# Monitor3.net
KiCad netlist of a schematic drawn in EAGLE
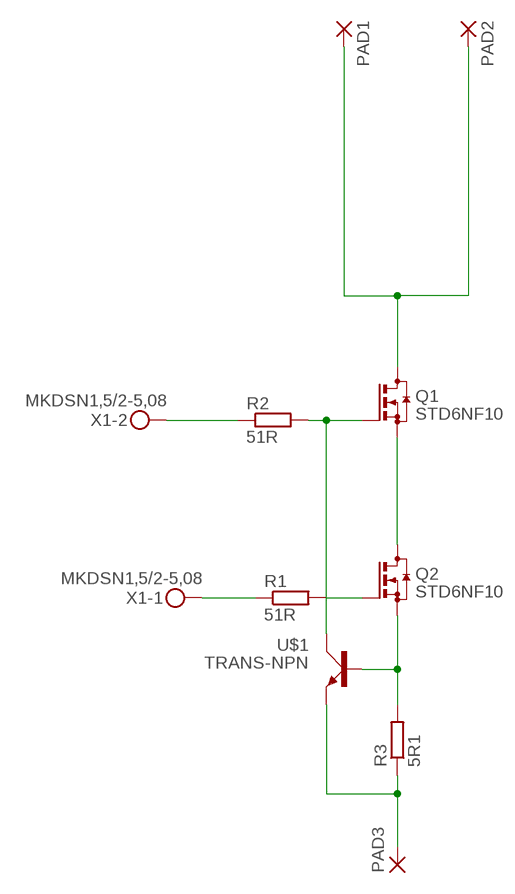
[diagram p0: schematic, sheet 1]

(export (version "E")
  (design (tool "Eeschema 10.0.6"))
  (components
    (comp (ref "PAD1")
      (value "3,81/1,4")
      (footprint "eagle-import:3,81_1,4")
      (libsource (lib "eagle-import") (part "3,81/1,4"))
    )
    (comp (ref "PAD2")
      (value "3,81/1,4")
      (footprint "eagle-import:3,81_1,4")
      (libsource (lib "eagle-import") (part "3,81/1,4"))
    )
    (comp (ref "PAD3")
      (value "3,81/1,4")
      (footprint "eagle-import:3,81_1,4")
      (libsource (lib "eagle-import") (part "3,81/1,4"))
    )
    (comp (ref "Q1")
      (value "STD6NF10")
      (footprint "eagle-import:DPAK")
      (libsource (lib "eagle-import") (part "STD6NF10"))
    )
    (comp (ref "Q2")
      (value "STD6NF10")
      (footprint "eagle-import:DPAK")
      (libsource (lib "eagle-import") (part "STD6NF10"))
    )
    (comp (ref "R1")
      (value "51R")
      (footprint "eagle-import:R0805")
      (libsource (lib "eagle-import") (part "R_0805"))
    )
    (comp (ref "R2")
      (value "51R")
      (footprint "eagle-import:R0805")
      (libsource (lib "eagle-import") (part "R_0805"))
    )
    (comp (ref "R3")
      (value "5R1")
      (footprint "eagle-import:R0805")
      (libsource (lib "eagle-import") (part "R_0805"))
    )
    (comp (ref "U$1")
      (value "TRANS-NPN")
      (footprint "eagle-import:SOT-92WIDE")
      (libsource (lib "eagle-import") (part "TRANS-NPN"))
    )
    (comp (ref "X1")
      (value "MKDSN1,5/2-5,08")
      (footprint "eagle-import:MKDSN1,5_2-5,08")
      (libsource (lib "eagle-import") (part "MKDSN1,5/2-5,08"))
    )
  )
  (nets
    (net (code "1") (name "Net-(PAD1-P)") (class "Default")
      (node (ref "PAD1") (pin "1") (pinfunction "P_1") (pintype "passive"))
      (node (ref "PAD2") (pin "1") (pinfunction "P_1") (pintype "passive"))
      (node (ref "Q1") (pin "D") (pinfunction "D_D") (pintype "passive"))
    )
    (net (code "2") (name "Net-(PAD3-P)") (class "Default")
      (node (ref "PAD3") (pin "1") (pinfunction "P_1") (pintype "passive"))
      (node (ref "R3") (pin "1") (pinfunction "1_1") (pintype "passive"))
      (node (ref "U$1") (pin "E") (pinfunction "E_E") (pintype "passive"))
    )
    (net (code "3") (name "Net-(Q1-PadG)") (class "Default")
      (node (ref "Q1") (pin "G") (pinfunction "G_G") (pintype "passive"))
      (node (ref "R2") (pin "2") (pinfunction "2_2") (pintype "passive"))
      (node (ref "U$1") (pin "C") (pinfunction "C_C") (pintype "passive"))
    )
    (net (code "4") (name "Net-(Q1-PadS)") (class "Default")
      (node (ref "Q1") (pin "S") (pinfunction "S_S") (pintype "passive"))
      (node (ref "Q2") (pin "D") (pinfunction "D_D") (pintype "passive"))
    )
    (net (code "5") (name "Net-(Q2-PadG)") (class "Default")
      (node (ref "Q2") (pin "G") (pinfunction "G_G") (pintype "passive"))
      (node (ref "R1") (pin "2") (pinfunction "2_2") (pintype "passive"))
    )
    (net (code "6") (name "Net-(Q2-PadS)") (class "Default")
      (node (ref "Q2") (pin "S") (pinfunction "S_S") (pintype "passive"))
      (node (ref "R3") (pin "2") (pinfunction "2_2") (pintype "passive"))
      (node (ref "U$1") (pin "B") (pinfunction "B_B") (pintype "passive"))
    )
    (net (code "7") (name "Net-(X1A-KL)") (class "Default")
      (node (ref "R1") (pin "1") (pinfunction "1_1") (pintype "passive"))
      (node (ref "X1") (pin "1") (pinfunction "KL_1") (pintype "passive"))
    )
    (net (code "8") (name "Net-(X1B-KL)") (class "Default")
      (node (ref "R2") (pin "1") (pinfunction "1_1") (pintype "passive"))
      (node (ref "X1") (pin "2") (pinfunction "KL_2") (pintype "passive"))
    )
  )
)
